# Manchester1593J.net
KiCad netlist of a schematic drawn in EAGLE
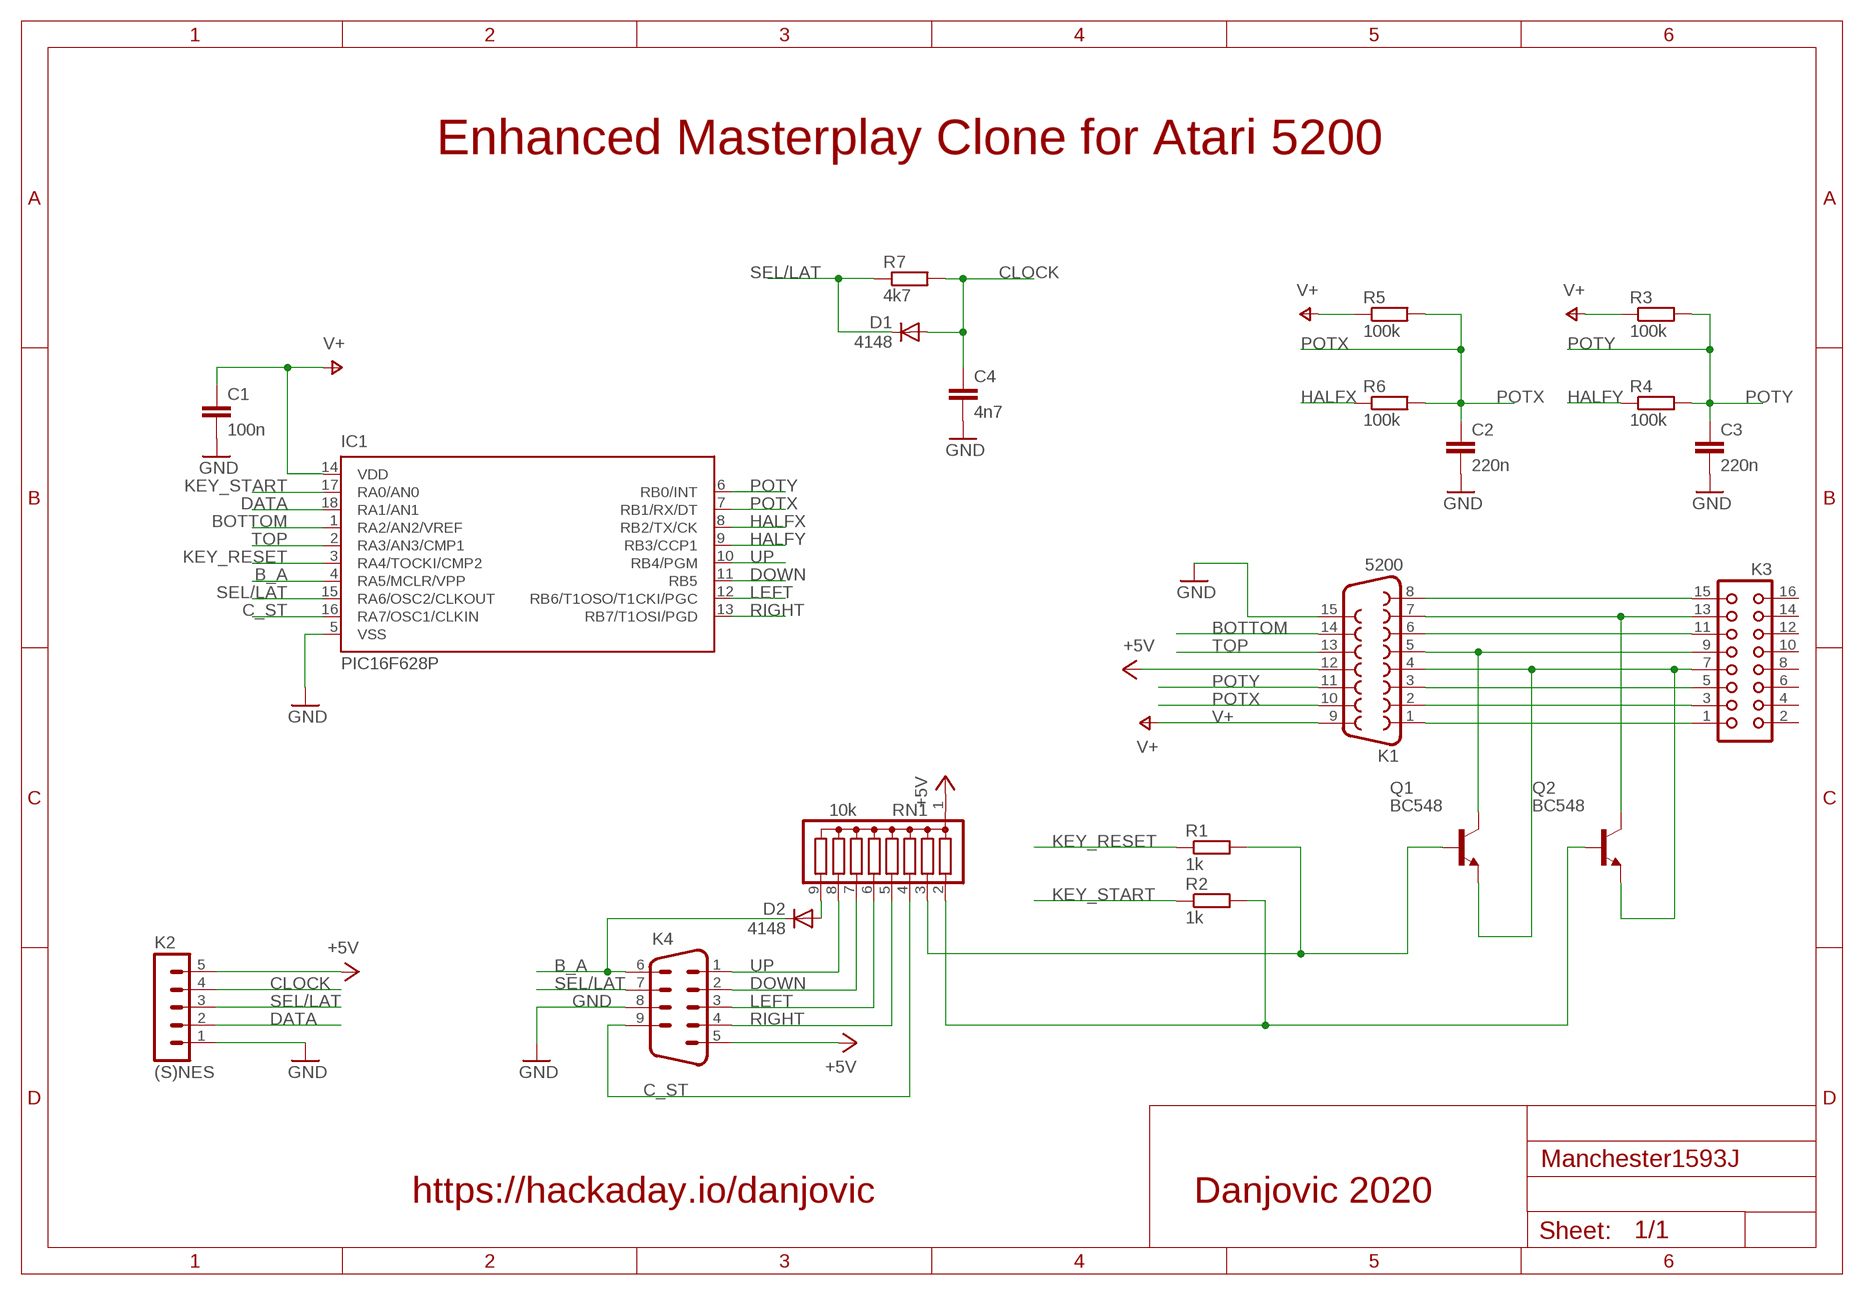
[diagram p0: schematic, sheet 1]

(export (version "E")
  (design (tool "Eeschema 10.0.6"))
  (components
    (comp (ref "C1")
      (value "100n")
      (footprint "eagle-import:C050-024X044")
      (libsource (lib "eagle-import") (part "C-EU050-024X044"))
    )
    (comp (ref "C2")
      (value "220n")
      (footprint "eagle-import:C050-024X044")
      (libsource (lib "eagle-import") (part "C-EU050-024X044"))
    )
    (comp (ref "C3")
      (value "220n")
      (footprint "eagle-import:C050-024X044")
      (libsource (lib "eagle-import") (part "C-EU050-024X044"))
    )
    (comp (ref "C4")
      (value "4n7")
      (footprint "eagle-import:C050-024X044")
      (libsource (lib "eagle-import") (part "C-EU050-024X044"))
    )
    (comp (ref "D1")
      (value "4148")
      (footprint "eagle-import:D-5")
      (libsource (lib "eagle-import") (part "DIODE-D-5"))
    )
    (comp (ref "D2")
      (value "4148")
      (footprint "eagle-import:D-5")
      (libsource (lib "eagle-import") (part "DIODE-D-5"))
    )
    (comp (ref "IC1")
      (value "PIC16F628P")
      (footprint "eagle-import:DIL18")
      (fields (field (name "MF") "MICROCHIP") (field (name "MPN") "PIC16F628-04I/P"))
      (libsource (lib "eagle-import") (part "PIC16F62P8"))
    )
    (comp (ref "K1")
      (value "5200")
      (footprint "eagle-import:F15H")
      (libsource (lib "eagle-import") (part "F15H"))
    )
    (comp (ref "K2")
      (value "(S)NES")
      (footprint "eagle-import:MA05-1")
      (libsource (lib "eagle-import") (part "MA05-1"))
    )
    (comp (ref "K3")
      (value "CON16L")
      (footprint "eagle-import:CON16L")
      (libsource (lib "eagle-import") (part "CON16L"))
    )
    (comp (ref "K4")
      (value "M09H")
      (footprint "eagle-import:M09H")
      (libsource (lib "eagle-import") (part "M09H"))
    )
    (comp (ref "Q1")
      (value "BC548")
      (footprint "eagle-import:TO92")
      (libsource (lib "eagle-import") (part "BC548"))
    )
    (comp (ref "Q2")
      (value "BC548")
      (footprint "eagle-import:TO92")
      (libsource (lib "eagle-import") (part "BC548"))
    )
    (comp (ref "R1")
      (value "1k")
      (footprint "eagle-import:0204_7")
      (libsource (lib "eagle-import") (part "R-EU_0204/7"))
    )
    (comp (ref "R2")
      (value "1k")
      (footprint "eagle-import:0204_7")
      (libsource (lib "eagle-import") (part "R-EU_0204/7"))
    )
    (comp (ref "R3")
      (value "100k")
      (footprint "eagle-import:0204_7")
      (libsource (lib "eagle-import") (part "R-EU_0204/7"))
    )
    (comp (ref "R4")
      (value "100k")
      (footprint "eagle-import:0204_7")
      (libsource (lib "eagle-import") (part "R-EU_0204/7"))
    )
    (comp (ref "R5")
      (value "100k")
      (footprint "eagle-import:0204_7")
      (libsource (lib "eagle-import") (part "R-EU_0204/7"))
    )
    (comp (ref "R6")
      (value "100k")
      (footprint "eagle-import:0204_7")
      (libsource (lib "eagle-import") (part "R-EU_0204/7"))
    )
    (comp (ref "R7")
      (value "4k7")
      (footprint "eagle-import:0204_7")
      (libsource (lib "eagle-import") (part "R-EU_0204/7"))
    )
    (comp (ref "RN1")
      (value "10k")
      (footprint "eagle-import:SIL9")
      (libsource (lib "eagle-import") (part "G08R"))
    )
  )
  (nets
    (net (code "1") (name "+5V") (class "Default")
      (node (ref "K1") (pin "12") (pinfunction "12_12") (pintype "passive"))
      (node (ref "K2") (pin "5") (pinfunction "5_5") (pintype "passive"))
      (node (ref "K4") (pin "5") (pinfunction "5_5") (pintype "passive"))
      (node (ref "RN1") (pin "1") (pinfunction "1_1") (pintype "passive"))
    )
    (net (code "2") (name "/BOTTOM") (class "Default")
      (node (ref "IC1") (pin "1") (pinfunction "RA2/AN2/VREF_1") (pintype "bidirectional"))
      (node (ref "K1") (pin "14") (pinfunction "14_14") (pintype "passive"))
    )
    (net (code "3") (name "/B_A") (class "Default")
      (node (ref "D2") (pin "C") (pinfunction "C_C") (pintype "passive"))
      (node (ref "IC1") (pin "4") (pinfunction "RA5/MCLR/VPP_4") (pintype "bidirectional"))
      (node (ref "K4") (pin "6") (pinfunction "6_6") (pintype "passive"))
    )
    (net (code "4") (name "/CLOCK") (class "Default")
      (node (ref "C4") (pin "1") (pinfunction "1_1") (pintype "passive"))
      (node (ref "D1") (pin "A") (pinfunction "A_A") (pintype "passive"))
      (node (ref "K2") (pin "4") (pinfunction "4_4") (pintype "passive"))
      (node (ref "R7") (pin "2") (pinfunction "2_2") (pintype "passive"))
    )
    (net (code "5") (name "/C_ST") (class "Default")
      (node (ref "IC1") (pin "16") (pinfunction "RA7/OSC1/CLKIN_16") (pintype "bidirectional"))
      (node (ref "K4") (pin "9") (pinfunction "9_9") (pintype "passive"))
      (node (ref "RN1") (pin "4") (pinfunction "4_4") (pintype "passive"))
    )
    (net (code "6") (name "/DATA") (class "Default")
      (node (ref "IC1") (pin "18") (pinfunction "RA1/AN1_18") (pintype "bidirectional"))
      (node (ref "K2") (pin "2") (pinfunction "2_2") (pintype "passive"))
    )
    (net (code "7") (name "/DOWN") (class "Default")
      (node (ref "IC1") (pin "11") (pinfunction "RB5_11") (pintype "bidirectional"))
      (node (ref "K4") (pin "2") (pinfunction "2_2") (pintype "passive"))
      (node (ref "RN1") (pin "7") (pinfunction "7_7") (pintype "passive"))
    )
    (net (code "8") (name "/HALFX") (class "Default")
      (node (ref "IC1") (pin "8") (pinfunction "RB2/TX/CK_8") (pintype "bidirectional"))
      (node (ref "R6") (pin "1") (pinfunction "1_1") (pintype "passive"))
    )
    (net (code "9") (name "/HALFY") (class "Default")
      (node (ref "IC1") (pin "9") (pinfunction "RB3/CCP1_9") (pintype "bidirectional"))
      (node (ref "R4") (pin "1") (pinfunction "1_1") (pintype "passive"))
    )
    (net (code "10") (name "/KEY_RESET") (class "Default")
      (node (ref "IC1") (pin "3") (pinfunction "RA4/TOCKI/CMP2_3") (pintype "bidirectional"))
      (node (ref "R1") (pin "1") (pinfunction "1_1") (pintype "passive"))
    )
    (net (code "11") (name "/KEY_START") (class "Default")
      (node (ref "IC1") (pin "17") (pinfunction "RA0/AN0_17") (pintype "bidirectional"))
      (node (ref "R2") (pin "1") (pinfunction "1_1") (pintype "passive"))
    )
    (net (code "12") (name "/LEFT") (class "Default")
      (node (ref "IC1") (pin "12") (pinfunction "RB6/T1OSO/T1CKI/PGC_12") (pintype "bidirectional"))
      (node (ref "K4") (pin "3") (pinfunction "3_3") (pintype "passive"))
      (node (ref "RN1") (pin "6") (pinfunction "6_6") (pintype "passive"))
    )
    (net (code "13") (name "/POTX") (class "Default")
      (node (ref "C2") (pin "1") (pinfunction "1_1") (pintype "passive"))
      (node (ref "IC1") (pin "7") (pinfunction "RB1/RX/DT_7") (pintype "bidirectional"))
      (node (ref "K1") (pin "10") (pinfunction "10_10") (pintype "passive"))
      (node (ref "R5") (pin "2") (pinfunction "2_2") (pintype "passive"))
      (node (ref "R6") (pin "2") (pinfunction "2_2") (pintype "passive"))
    )
    (net (code "14") (name "/POTY") (class "Default")
      (node (ref "C3") (pin "1") (pinfunction "1_1") (pintype "passive"))
      (node (ref "IC1") (pin "6") (pinfunction "RB0/INT_6") (pintype "bidirectional"))
      (node (ref "K1") (pin "11") (pinfunction "11_11") (pintype "passive"))
      (node (ref "R3") (pin "2") (pinfunction "2_2") (pintype "passive"))
      (node (ref "R4") (pin "2") (pinfunction "2_2") (pintype "passive"))
    )
    (net (code "15") (name "/RIGHT") (class "Default")
      (node (ref "IC1") (pin "13") (pinfunction "RB7/T1OSI/PGD_13") (pintype "bidirectional"))
      (node (ref "K4") (pin "4") (pinfunction "4_4") (pintype "passive"))
      (node (ref "RN1") (pin "5") (pinfunction "5_5") (pintype "passive"))
    )
    (net (code "16") (name "/SEL{slash}LAT") (class "Default")
      (node (ref "D1") (pin "C") (pinfunction "C_C") (pintype "passive"))
      (node (ref "IC1") (pin "15") (pinfunction "RA6/OSC2/CLKOUT_15") (pintype "bidirectional"))
      (node (ref "K2") (pin "3") (pinfunction "3_3") (pintype "passive"))
      (node (ref "K4") (pin "7") (pinfunction "7_7") (pintype "passive"))
      (node (ref "R7") (pin "1") (pinfunction "1_1") (pintype "passive"))
    )
    (net (code "17") (name "/TOP") (class "Default")
      (node (ref "IC1") (pin "2") (pinfunction "RA3/AN3/CMP1_2") (pintype "bidirectional"))
      (node (ref "K1") (pin "13") (pinfunction "13_13") (pintype "passive"))
    )
    (net (code "18") (name "/UP") (class "Default")
      (node (ref "IC1") (pin "10") (pinfunction "RB4/PGM_10") (pintype "bidirectional"))
      (node (ref "K4") (pin "1") (pinfunction "1_1") (pintype "passive"))
      (node (ref "RN1") (pin "8") (pinfunction "8_8") (pintype "passive"))
    )
    (net (code "19") (name "GND") (class "Default")
      (node (ref "C1") (pin "2") (pinfunction "2_2") (pintype "passive"))
      (node (ref "C2") (pin "2") (pinfunction "2_2") (pintype "passive"))
      (node (ref "C3") (pin "2") (pinfunction "2_2") (pintype "passive"))
      (node (ref "C4") (pin "2") (pinfunction "2_2") (pintype "passive"))
      (node (ref "IC1") (pin "5") (pinfunction "VSS_5") (pintype "power_in"))
      (node (ref "K1") (pin "15") (pinfunction "15_15") (pintype "passive"))
      (node (ref "K2") (pin "1") (pinfunction "1_1") (pintype "passive"))
      (node (ref "K4") (pin "8") (pinfunction "8_8") (pintype "passive"))
    )
    (net (code "20") (name "Net-(D2-PadA)") (class "Default")
      (node (ref "D2") (pin "A") (pinfunction "A_A") (pintype "passive"))
      (node (ref "RN1") (pin "9") (pinfunction "9_9") (pintype "passive"))
    )
    (net (code "21") (name "Net-(K1-Pad1)") (class "Default")
      (node (ref "K1") (pin "1") (pinfunction "1_1") (pintype "passive"))
      (node (ref "K3") (pin "1") (pinfunction "1_1") (pintype "passive"))
    )
    (net (code "22") (name "Net-(K1-Pad2)") (class "Default")
      (node (ref "K1") (pin "2") (pinfunction "2_2") (pintype "passive"))
      (node (ref "K3") (pin "3") (pinfunction "3_3") (pintype "passive"))
    )
    (net (code "23") (name "Net-(K1-Pad3)") (class "Default")
      (node (ref "K1") (pin "3") (pinfunction "3_3") (pintype "passive"))
      (node (ref "K3") (pin "5") (pinfunction "5_5") (pintype "passive"))
    )
    (net (code "24") (name "Net-(K1-Pad6)") (class "Default")
      (node (ref "K1") (pin "6") (pinfunction "6_6") (pintype "passive"))
      (node (ref "K3") (pin "11") (pinfunction "11_11") (pintype "passive"))
    )
    (net (code "25") (name "Net-(K1-Pad8)") (class "Default")
      (node (ref "K1") (pin "8") (pinfunction "8_8") (pintype "passive"))
      (node (ref "K3") (pin "15") (pinfunction "15_15") (pintype "passive"))
    )
    (net (code "26") (name "Net-(Q1-B)") (class "Default")
      (node (ref "Q1") (pin "2") (pinfunction "B_2") (pintype "passive"))
      (node (ref "R1") (pin "2") (pinfunction "2_2") (pintype "passive"))
      (node (ref "RN1") (pin "3") (pinfunction "3_3") (pintype "passive"))
    )
    (net (code "27") (name "Net-(Q1-C)") (class "Default")
      (node (ref "K1") (pin "5") (pinfunction "5_5") (pintype "passive"))
      (node (ref "K3") (pin "9") (pinfunction "9_9") (pintype "passive"))
      (node (ref "Q1") (pin "3") (pinfunction "C_3") (pintype "passive"))
    )
    (net (code "28") (name "Net-(Q1-E)") (class "Default")
      (node (ref "K1") (pin "4") (pinfunction "4_4") (pintype "passive"))
      (node (ref "K3") (pin "7") (pinfunction "7_7") (pintype "passive"))
      (node (ref "Q1") (pin "1") (pinfunction "E_1") (pintype "passive"))
      (node (ref "Q2") (pin "1") (pinfunction "E_1") (pintype "passive"))
    )
    (net (code "29") (name "Net-(Q2-B)") (class "Default")
      (node (ref "Q2") (pin "2") (pinfunction "B_2") (pintype "passive"))
      (node (ref "R2") (pin "2") (pinfunction "2_2") (pintype "passive"))
      (node (ref "RN1") (pin "2") (pinfunction "2_2") (pintype "passive"))
    )
    (net (code "30") (name "Net-(Q2-C)") (class "Default")
      (node (ref "K1") (pin "7") (pinfunction "7_7") (pintype "passive"))
      (node (ref "K3") (pin "13") (pinfunction "13_13") (pintype "passive"))
      (node (ref "Q2") (pin "3") (pinfunction "C_3") (pintype "passive"))
    )
    (net (code "31") (name "V+") (class "Default")
      (node (ref "C1") (pin "1") (pinfunction "1_1") (pintype "passive"))
      (node (ref "IC1") (pin "14") (pinfunction "VDD_14") (pintype "power_in"))
      (node (ref "K1") (pin "9") (pinfunction "9_9") (pintype "passive"))
      (node (ref "R3") (pin "1") (pinfunction "1_1") (pintype "passive"))
      (node (ref "R5") (pin "1") (pinfunction "1_1") (pintype "passive"))
    )
    (net (code "32") (name "unconnected-(K3-Pad2)") (class "Default")
      (node (ref "K3") (pin "2") (pinfunction "2_2") (pintype "passive"))
    )
    (net (code "33") (name "unconnected-(K3-Pad4)") (class "Default")
      (node (ref "K3") (pin "4") (pinfunction "4_4") (pintype "passive"))
    )
    (net (code "34") (name "unconnected-(K3-Pad6)") (class "Default")
      (node (ref "K3") (pin "6") (pinfunction "6_6") (pintype "passive"))
    )
    (net (code "35") (name "unconnected-(K3-Pad8)") (class "Default")
      (node (ref "K3") (pin "8") (pinfunction "8_8") (pintype "passive"))
    )
    (net (code "36") (name "unconnected-(K3-Pad10)") (class "Default")
      (node (ref "K3") (pin "10") (pinfunction "10_10") (pintype "passive"))
    )
    (net (code "37") (name "unconnected-(K3-Pad12)") (class "Default")
      (node (ref "K3") (pin "12") (pinfunction "12_12") (pintype "passive"))
    )
    (net (code "38") (name "unconnected-(K3-Pad14)") (class "Default")
      (node (ref "K3") (pin "14") (pinfunction "14_14") (pintype "passive"))
    )
    (net (code "39") (name "unconnected-(K3-Pad16)") (class "Default")
      (node (ref "K3") (pin "16") (pinfunction "16_16") (pintype "passive"))
    )
  )
)
